# 4_Sensoren.net
KiCad netlist of a schematic drawn in Altium Designer
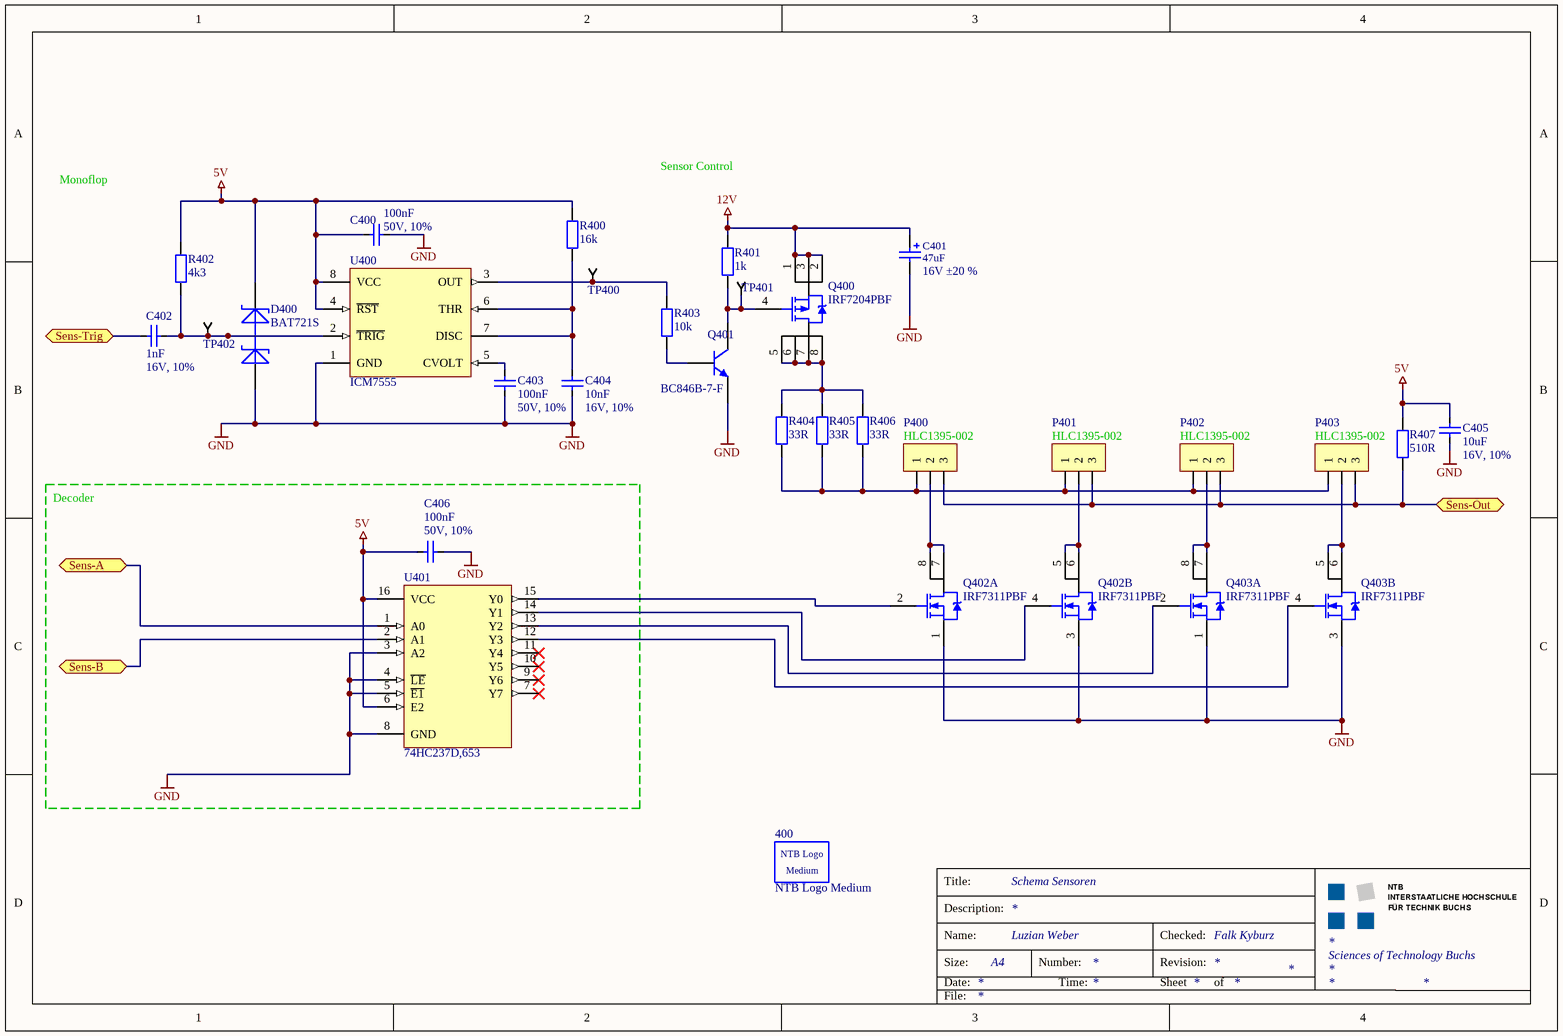
[diagram p0: 4_Sensoren.SchDoc]

(export (version "E")
  (design (tool "Eeschema 10.0.6"))
  (components
    (comp (ref "400")
      (value "NTB Logo Medium")
      (footprint "NTB Logo Medium")
      (libsource (lib "IR-Sensor") (part "NTB Logo Medium"))
    )
    (comp (ref "C400")
      (value "100nF")
      (footprint "CAP-0805[2012]")
      (description "100n 50V X7R MLCC 0805 (1608 Metric)")
      (fields (field (name "TOLERANCE") "10%") (field (name "VALADDON") "50V, 10%"))
      (libsource (lib "IR-Sensor") (part "MLCC 0805 100n 50V"))
    )
    (comp (ref "C401")
      (value "47uF")
      (footprint "CDE_CAP AVE CODE D_H")
      (description "ELKO, 47uF, 16V, CDE_AVE476M16D16T-F_AVE CODE D")
      (fields
        (field (name "MANUFACTURER") "Cornell Dubilier")
        (field (name "VALUEADDON") "16V ±20 %")
        (field (name "Comment") "AVE476M16D16T-F")
        (field (name "PUBLISHER") "Stefan Ursella, M.Eng")
      )
      (libsource (lib "IR-Sensor") (part "ELKO 47uF 16V"))
    )
    (comp (ref "C402")
      (value "1nF")
      (footprint "CAP-0805[2012]")
      (description "MLCC - SMD/SMT 0805 1000pF 16V C0G 10%")
      (fields
        (field (name "MANUFACTURER") "Vishay")
        (field (name "VALUEADDON") "16V, 10%")
        (field (name "PUBLISHER") "SCLM")
      )
      (libsource (lib "IR-Sensor") (part "MLCC 0805 1n 16V"))
    )
    (comp (ref "C403")
      (value "100nF")
      (footprint "CAP-0805[2012]")
      (description "100n 50V X7R MLCC 0805 (1608 Metric)")
      (fields (field (name "TOLERANCE") "10%") (field (name "VALADDON") "50V, 10%"))
      (libsource (lib "IR-Sensor") (part "MLCC 0805 100n 50V"))
    )
    (comp (ref "C404")
      (value "10nF")
      (footprint "CAP-0805[2012]")
      (description "10n 16V X7R MLCC 0805")
      (fields
        (field (name "MANUFACTURER") "AVX")
        (field (name "VALUEADDON") "16V, 10%")
        (field (name "PUBLISHER") "SCLM")
      )
      (libsource (lib "IR-Sensor") (part "MLCC 0805 10n 16V"))
    )
    (comp (ref "C405")
      (value "10uF")
      (footprint "CAP-1206[3216]")
      (description "10u 16V X7R MLCC 1206 (3016 Metric)")
      (fields (field (name "TOLERANCE") "10%") (field (name "VALADDON") "16V, 10%"))
      (libsource (lib "IR-Sensor") (part "MLCC 1206 10u 16V"))
    )
    (comp (ref "C406")
      (value "100nF")
      (footprint "CAP-0805[2012]")
      (description "100n 50V X7R MLCC 0805 (1608 Metric)")
      (fields (field (name "TOLERANCE") "10%") (field (name "VALADDON") "50V, 10%"))
      (libsource (lib "IR-Sensor") (part "MLCC 0805 100n 50V"))
    )
    (comp (ref "D400")
      (value "BAT721S")
      (footprint "SOT-23")
      (description "NXP  BAT721S  SCHOTTKY-DIODE, 2FACH")
      (fields (field (name "MANUFACTURER") "NXP") (field (name "PUBLISHER") "SCNP"))
      (libsource (lib "IR-Sensor") (part "BAT721S-SOT23"))
    )
    (comp (ref "P400")
      (value "3 Pin Header Buchse")
      (footprint "3PIN HEADER SOCKET 2.54MM")
      (description "3 Pin Header 2.54mm Buchse")
      (libsource (lib "IR-Sensor") (part "3 Pin Header Buchse"))
    )
    (comp (ref "P401")
      (value "3 Pin Header Buchse")
      (footprint "3PIN HEADER SOCKET 2.54MM")
      (description "3 Pin Header 2.54mm Buchse")
      (libsource (lib "IR-Sensor") (part "3 Pin Header Buchse"))
    )
    (comp (ref "P402")
      (value "3 Pin Header Buchse")
      (footprint "3PIN HEADER SOCKET 2.54MM")
      (description "3 Pin Header 2.54mm Buchse")
      (libsource (lib "IR-Sensor") (part "3 Pin Header Buchse"))
    )
    (comp (ref "P403")
      (value "3 Pin Header Buchse")
      (footprint "3PIN HEADER SOCKET 2.54MM")
      (description "3 Pin Header 2.54mm Buchse")
      (libsource (lib "IR-Sensor") (part "3 Pin Header Buchse"))
    )
    (comp (ref "Q400")
      (value "IRF7204PBF")
      (footprint "SOIC-8")
      (description "High Power P-Kanal Mosfet")
      (fields
        (field (name "MANUFACTURER") "International Rectifiers")
        (field (name "PUBLISHER") "Altium Limited")
      )
      (libsource (lib "IR-Sensor") (part "IRF7204"))
    )
    (comp (ref "Q401")
      (value "BC846B-7-F")
      (footprint "SOT-23")
      (description "NPN General-purpose Transistor")
      (fields (field (name "MANUFACTURER") "DIODES INC") (field (name "PUBLISHER") "Altium Limited"))
      (libsource (lib "IR-Sensor") (part "BC846B-SOT23"))
    )
    (comp (ref "Q402")
      (value "IRF7311PBF")
      (footprint "SOIC-8")
      (description "Dual N-Kanal Mosfet")
      (fields
        (field (name "MANUFACTURER") "International Rectifier")
        (field (name "PUBLISHER") "Altium Limited")
      )
      (libsource (lib "IR-Sensor") (part "IRF7311"))
    )
    (comp (ref "Q403")
      (value "IRF7311PBF")
      (footprint "SOIC-8")
      (description "Dual N-Kanal Mosfet")
      (fields
        (field (name "MANUFACTURER") "International Rectifier")
        (field (name "PUBLISHER") "Altium Limited")
      )
      (libsource (lib "IR-Sensor") (part "IRF7311"))
    )
    (comp (ref "R400")
      (value "16k")
      (footprint "RES-0805[2012]")
      (description "0805 (2013 Metric) 1/10 W 10K 1 Thick Film Chip Resistor")
      (fields (field (name "POWER") "1/10 W") (field (name "TOLERANCE") "1%"))
      (libsource (lib "IR-Sensor") (part "RES 0805"))
    )
    (comp (ref "R401")
      (value "1k")
      (footprint "RES-0805[2012]")
      (description "0805 (2013 Metric) 1/10 W 10K 1 Thick Film Chip Resistor")
      (fields (field (name "POWER") "1/10 W") (field (name "TOLERANCE") "1%"))
      (libsource (lib "IR-Sensor") (part "RES 0805"))
    )
    (comp (ref "R402")
      (value "4k3")
      (footprint "RES-0805[2012]")
      (description "0805 (2013 Metric) 1/10 W 10K 1 Thick Film Chip Resistor")
      (fields (field (name "POWER") "1/10 W") (field (name "TOLERANCE") "1%"))
      (libsource (lib "IR-Sensor") (part "RES 0805"))
    )
    (comp (ref "R403")
      (value "10k")
      (footprint "RES-0805[2012]")
      (description "0805 (2013 Metric) 1/10 W 10K 1 Thick Film Chip Resistor")
      (fields (field (name "POWER") "1/10 W") (field (name "TOLERANCE") "1%"))
      (libsource (lib "IR-Sensor") (part "RES 0805"))
    )
    (comp (ref "R404")
      (value "33R")
      (footprint "RES-0805[2012]")
      (description "0805 (2013 Metric) 1/10 W 10K 1 Thick Film Chip Resistor")
      (fields (field (name "POWER") "1/10 W") (field (name "TOLERANCE") "1%"))
      (libsource (lib "IR-Sensor") (part "RES 0805"))
    )
    (comp (ref "R405")
      (value "33R")
      (footprint "RES-0805[2012]")
      (description "0805 (2013 Metric) 1/10 W 10K 1 Thick Film Chip Resistor")
      (fields (field (name "POWER") "1/10 W") (field (name "TOLERANCE") "1%"))
      (libsource (lib "IR-Sensor") (part "RES 0805"))
    )
    (comp (ref "R406")
      (value "33R")
      (footprint "RES-0805[2012]")
      (description "0805 (2013 Metric) 1/10 W 10K 1 Thick Film Chip Resistor")
      (fields (field (name "POWER") "1/10 W") (field (name "TOLERANCE") "1%"))
      (libsource (lib "IR-Sensor") (part "RES 0805"))
    )
    (comp (ref "R407")
      (value "510R")
      (footprint "RES-0805[2012]")
      (description "0805 (2013 Metric) 1/10 W 10K 1 Thick Film Chip Resistor")
      (fields (field (name "POWER") "1/10 W") (field (name "TOLERANCE") "1%"))
      (libsource (lib "IR-Sensor") (part "RES 0805"))
    )
    (comp (ref "TP400")
      (value "Testpoint SMD 1206")
      (footprint "TP-SMD-1206")
      (description "Testpoint xSmall")
      (libsource (lib "IR-Sensor") (part "Testpoint SMD 1206"))
    )
    (comp (ref "TP401")
      (value "Testpoint SMD 1206")
      (footprint "TP-SMD-1206")
      (description "Testpoint xSmall")
      (libsource (lib "altium-import") (part "root_0_Testpoint SMD 1206_"))
    )
    (comp (ref "TP402")
      (value "Testpoint SMD 1206")
      (footprint "TP-SMD-1206")
      (description "Testpoint xSmall")
      (libsource (lib "IR-Sensor") (part "Testpoint SMD 1206"))
    )
    (comp (ref "U400")
      (value "ICM7555")
      (footprint "SOIC-8")
      (description "General purpose CMOS timer")
      (fields
        (field (name "MANUFACTURER") "National Semiconductor")
        (field (name "PUBLISHER") "Altium Hobart Technology Centre")
      )
      (libsource (lib "IR-Sensor") (part "ICM7555-SOIC8"))
    )
    (comp (ref "U401")
      (value "74HC237D,653")
      (footprint "SOIC-16")
      (description "3-to-8 line decoder, demultiplexer, NXP, SO16")
      (fields (field (name "MANUFACTURER") "NXP") (field (name "PUBLISHER") "SCLM"))
      (libsource (lib "IR-Sensor") (part "74HC237D-SOIC16"))
    )
  )
  (nets
    (net (code "1") (name "/Sens-A") (class "Default")
      (node (ref "U401") (pin "1") (pinfunction "A0_1") (pintype "input"))
    )
    (net (code "2") (name "/Sens-B") (class "Default")
      (node (ref "U401") (pin "2") (pinfunction "A1_2") (pintype "input"))
    )
    (net (code "3") (name "/Sens-Out") (class "Default")
      (node (ref "P400") (pin "3") (pinfunction "3_3") (pintype "passive"))
      (node (ref "P401") (pin "3") (pinfunction "3_3") (pintype "passive"))
      (node (ref "P402") (pin "3") (pinfunction "3_3") (pintype "passive"))
      (node (ref "P403") (pin "3") (pinfunction "3_3") (pintype "passive"))
      (node (ref "R407") (pin "1") (pinfunction "1_1") (pintype "passive"))
    )
    (net (code "4") (name "/Sens-Trig") (class "Default")
      (node (ref "C402") (pin "1") (pinfunction "Pos_1") (pintype "passive"))
    )
    (net (code "5") (name "5V") (class "Default")
      (node (ref "C400") (pin "1") (pinfunction "Pos_1") (pintype "passive"))
      (node (ref "C405") (pin "1") (pinfunction "Pos_1") (pintype "passive"))
      (node (ref "C406") (pin "1") (pinfunction "Pos_1") (pintype "passive"))
      (node (ref "D400") (pin "2") (pinfunction "cathode2_2") (pintype "passive"))
      (node (ref "R400") (pin "2") (pinfunction "2_2") (pintype "passive"))
      (node (ref "R402") (pin "2") (pinfunction "2_2") (pintype "passive"))
      (node (ref "R407") (pin "2") (pinfunction "2_2") (pintype "passive"))
      (node (ref "U400") (pin "4") (pinfunction "~{RST}_4") (pintype "input"))
      (node (ref "U400") (pin "8") (pinfunction "VCC_8") (pintype "power_in"))
      (node (ref "U401") (pin "16") (pinfunction "VCC_16") (pintype "power_in"))
      (node (ref "U401") (pin "6") (pinfunction "E2_6") (pintype "input"))
    )
    (net (code "6") (name "12V") (class "Default")
      (node (ref "C401") (pin "1") (pinfunction "Pos_1") (pintype "passive"))
      (node (ref "Q400") (pin "1") (pinfunction "S_1") (pintype "passive"))
      (node (ref "Q400") (pin "2") (pinfunction "S_2") (pintype "passive"))
      (node (ref "Q400") (pin "3") (pinfunction "S_3") (pintype "passive"))
      (node (ref "R401") (pin "2") (pinfunction "2_2") (pintype "passive"))
    )
    (net (code "7") (name "GND") (class "Default")
      (node (ref "C400") (pin "2") (pinfunction "Neg_2") (pintype "passive"))
      (node (ref "C401") (pin "2") (pinfunction "Neg_2") (pintype "passive"))
      (node (ref "C403") (pin "2") (pinfunction "Neg_2") (pintype "passive"))
      (node (ref "C404") (pin "2") (pinfunction "Neg_2") (pintype "passive"))
      (node (ref "C405") (pin "2") (pinfunction "Neg_2") (pintype "passive"))
      (node (ref "C406") (pin "2") (pinfunction "Neg_2") (pintype "passive"))
      (node (ref "D400") (pin "1") (pinfunction "Anode1_1") (pintype "passive"))
      (node (ref "Q401") (pin "2") (pinfunction "E_2") (pintype "passive"))
      (node (ref "Q402") (pin "1") (pinfunction "S_1") (pintype "passive"))
      (node (ref "Q402") (pin "3") (pinfunction "S_3") (pintype "passive"))
      (node (ref "Q403") (pin "1") (pinfunction "S_1") (pintype "passive"))
      (node (ref "Q403") (pin "3") (pinfunction "S_3") (pintype "passive"))
      (node (ref "U400") (pin "1") (pinfunction "GND_1") (pintype "power_in"))
      (node (ref "U401") (pin "3") (pinfunction "A2_3") (pintype "input"))
      (node (ref "U401") (pin "4") (pinfunction "LE_4") (pintype "input"))
      (node (ref "U401") (pin "5") (pinfunction "E1_5") (pintype "input"))
      (node (ref "U401") (pin "8") (pinfunction "GND_8") (pintype "power_in"))
    )
    (net (code "8") (name "Net-(C402-Neg)") (class "Default")
      (node (ref "C402") (pin "2") (pinfunction "Neg_2") (pintype "passive"))
      (node (ref "D400") (pin "3") (pinfunction "Cathode1,_anode2_3") (pintype "passive"))
      (node (ref "R402") (pin "1") (pinfunction "1_1") (pintype "passive"))
      (node (ref "TP402") (pin "1") (pinfunction "0_1") (pintype "passive"))
      (node (ref "U400") (pin "2") (pinfunction "TRIG_2") (pintype "input"))
    )
    (net (code "9") (name "Net-(C403-Pos)") (class "Default")
      (node (ref "C403") (pin "1") (pinfunction "Pos_1") (pintype "passive"))
      (node (ref "U400") (pin "5") (pinfunction "CVOLT_5") (pintype "input"))
    )
    (net (code "10") (name "Net-(C404-Pos)") (class "Default")
      (node (ref "C404") (pin "1") (pinfunction "Pos_1") (pintype "passive"))
      (node (ref "R400") (pin "1") (pinfunction "1_1") (pintype "passive"))
      (node (ref "U400") (pin "6") (pinfunction "THR_6") (pintype "input"))
      (node (ref "U400") (pin "7") (pinfunction "DISC_7") (pintype "open_collector"))
    )
    (net (code "11") (name "Net-(P400-Pad1)") (class "Default")
      (node (ref "P400") (pin "1") (pinfunction "1_1") (pintype "passive"))
      (node (ref "P401") (pin "1") (pinfunction "1_1") (pintype "passive"))
      (node (ref "P402") (pin "1") (pinfunction "1_1") (pintype "passive"))
      (node (ref "P403") (pin "1") (pinfunction "1_1") (pintype "passive"))
      (node (ref "R404") (pin "1") (pinfunction "1_1") (pintype "passive"))
      (node (ref "R405") (pin "1") (pinfunction "1_1") (pintype "passive"))
      (node (ref "R406") (pin "1") (pinfunction "1_1") (pintype "passive"))
    )
    (net (code "12") (name "Net-(P400-Pad2)") (class "Default")
      (node (ref "P400") (pin "2") (pinfunction "2_2") (pintype "passive"))
      (node (ref "Q402") (pin "7") (pinfunction "D_7") (pintype "passive"))
      (node (ref "Q402") (pin "8") (pinfunction "D_8") (pintype "passive"))
    )
    (net (code "13") (name "Net-(P401-Pad2)") (class "Default")
      (node (ref "P401") (pin "2") (pinfunction "2_2") (pintype "passive"))
      (node (ref "Q402") (pin "5") (pinfunction "D_5") (pintype "passive"))
      (node (ref "Q402") (pin "6") (pinfunction "D_6") (pintype "passive"))
    )
    (net (code "14") (name "Net-(P402-Pad2)") (class "Default")
      (node (ref "P402") (pin "2") (pinfunction "2_2") (pintype "passive"))
      (node (ref "Q403") (pin "7") (pinfunction "D_7") (pintype "passive"))
      (node (ref "Q403") (pin "8") (pinfunction "D_8") (pintype "passive"))
    )
    (net (code "15") (name "Net-(P403-Pad2)") (class "Default")
      (node (ref "P403") (pin "2") (pinfunction "2_2") (pintype "passive"))
      (node (ref "Q403") (pin "5") (pinfunction "D_5") (pintype "passive"))
      (node (ref "Q403") (pin "6") (pinfunction "D_6") (pintype "passive"))
    )
    (net (code "16") (name "Net-(Q400-D-Pad5)") (class "Default")
      (node (ref "Q400") (pin "5") (pinfunction "D_5") (pintype "passive"))
      (node (ref "Q400") (pin "6") (pinfunction "D_6") (pintype "passive"))
      (node (ref "Q400") (pin "7") (pinfunction "D_7") (pintype "passive"))
      (node (ref "Q400") (pin "8") (pinfunction "D_8") (pintype "passive"))
      (node (ref "R404") (pin "2") (pinfunction "2_2") (pintype "passive"))
      (node (ref "R405") (pin "2") (pinfunction "2_2") (pintype "passive"))
      (node (ref "R406") (pin "2") (pinfunction "2_2") (pintype "passive"))
    )
    (net (code "17") (name "Net-(Q400-G)") (class "Default")
      (node (ref "Q400") (pin "4") (pinfunction "G_4") (pintype "passive"))
      (node (ref "Q401") (pin "3") (pinfunction "C_3") (pintype "passive"))
      (node (ref "R401") (pin "1") (pinfunction "1_1") (pintype "passive"))
      (node (ref "TP401") (pin "1") (pinfunction "0_1") (pintype "passive"))
    )
    (net (code "18") (name "Net-(Q401-B)") (class "Default")
      (node (ref "Q401") (pin "1") (pinfunction "B_1") (pintype "passive"))
      (node (ref "R403") (pin "2") (pinfunction "2_2") (pintype "passive"))
    )
    (net (code "19") (name "Net-(Q402A-G)") (class "Default")
      (node (ref "Q402") (pin "2") (pinfunction "G_2") (pintype "passive"))
      (node (ref "U401") (pin "15") (pinfunction "Y0_15") (pintype "output"))
    )
    (net (code "20") (name "Net-(Q402B-G)") (class "Default")
      (node (ref "Q402") (pin "4") (pinfunction "G_4") (pintype "passive"))
      (node (ref "U401") (pin "14") (pinfunction "Y1_14") (pintype "output"))
    )
    (net (code "21") (name "Net-(Q403A-G)") (class "Default")
      (node (ref "Q403") (pin "2") (pinfunction "G_2") (pintype "passive"))
      (node (ref "U401") (pin "13") (pinfunction "Y2_13") (pintype "output"))
    )
    (net (code "22") (name "Net-(Q403B-G)") (class "Default")
      (node (ref "Q403") (pin "4") (pinfunction "G_4") (pintype "passive"))
      (node (ref "U401") (pin "12") (pinfunction "Y3_12") (pintype "output"))
    )
    (net (code "23") (name "Net-(TP400-0)") (class "Default")
      (node (ref "R403") (pin "1") (pinfunction "1_1") (pintype "passive"))
      (node (ref "TP400") (pin "1") (pinfunction "0_1") (pintype "passive"))
      (node (ref "U400") (pin "3") (pinfunction "OUT_3") (pintype "output"))
    )
    (net (code "24") (name "unconnected-(U401-Y4-Pad11)") (class "Default")
      (node (ref "U401") (pin "11") (pinfunction "Y4_11") (pintype "output+no_connect"))
    )
    (net (code "25") (name "unconnected-(U401-Y5-Pad10)") (class "Default")
      (node (ref "U401") (pin "10") (pinfunction "Y5_10") (pintype "output+no_connect"))
    )
    (net (code "26") (name "unconnected-(U401-Y6-Pad9)") (class "Default")
      (node (ref "U401") (pin "9") (pinfunction "Y6_9") (pintype "output+no_connect"))
    )
    (net (code "27") (name "unconnected-(U401-Y7-Pad7)") (class "Default")
      (node (ref "U401") (pin "7") (pinfunction "Y7_7") (pintype "output+no_connect"))
    )
  )
)
